# etf_pwr.net
KiCad netlist of a schematic drawn in Altium Designer
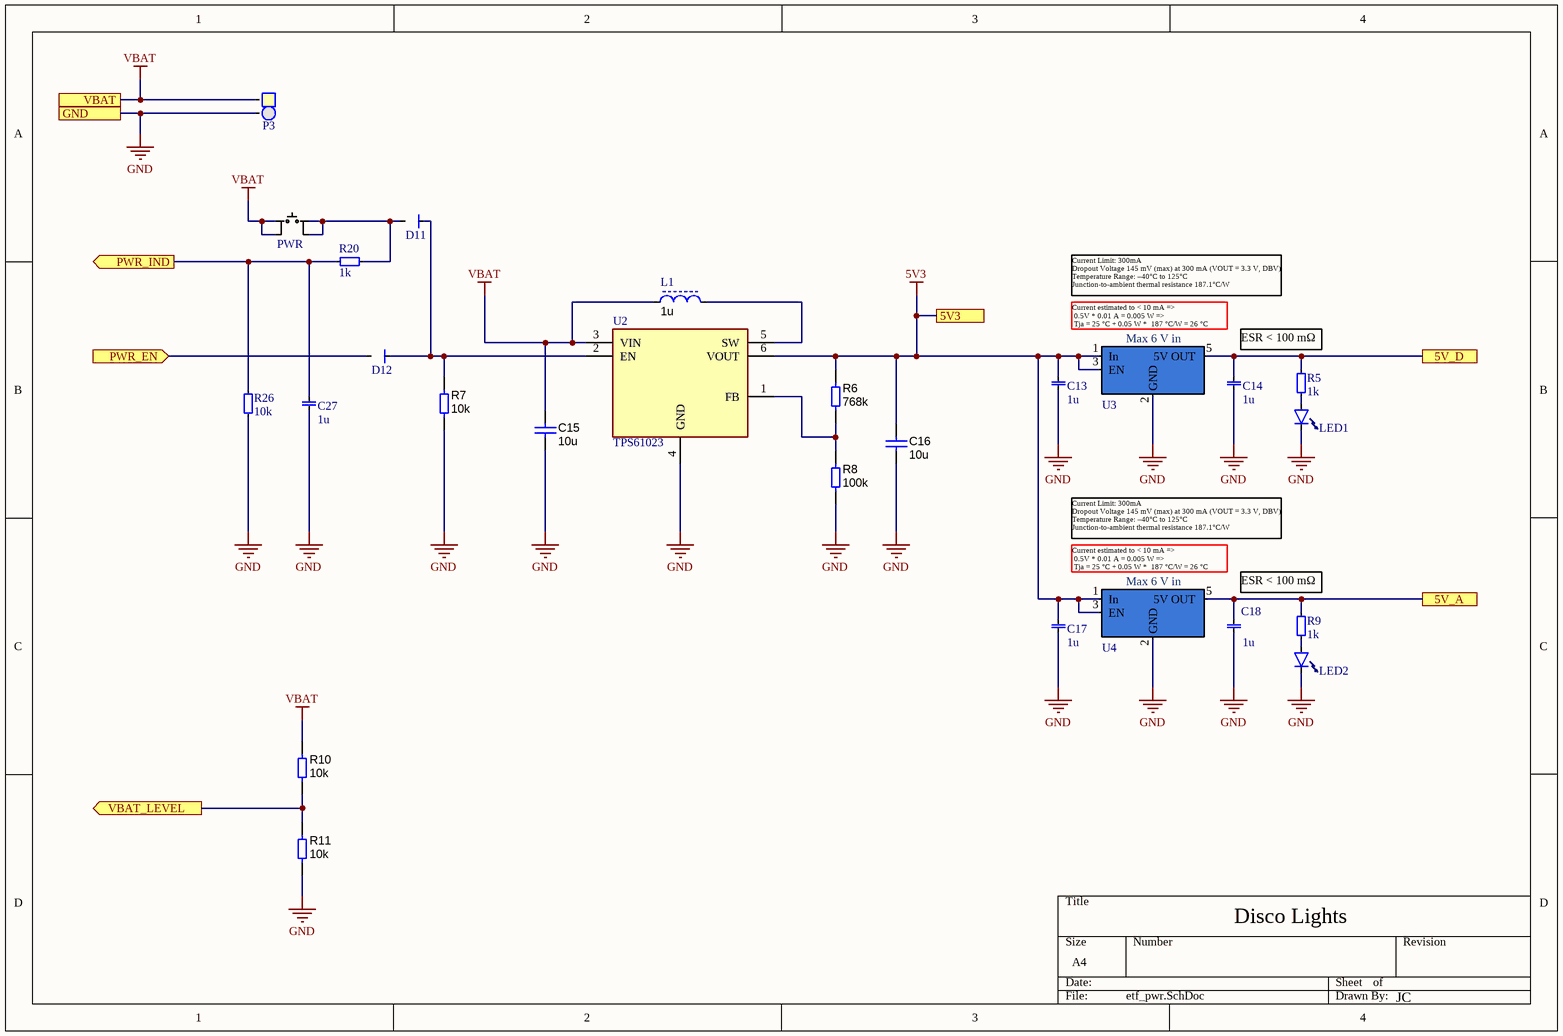
[diagram p0: etf_pwr.SchDoc]

(export (version "E")
  (design (tool "Eeschema 10.0.6"))
  (components
    (comp (ref "C13")
      (value "1u")
      (footprint "0603 cap")
      (fields
        (field (name "JLCPCB PART #") "C77386")
        (field (name "MANUFACTURER PART NUMBER") "GRM188R61H105KAALD")
        (field (name "Comment") "0603, capacitor")
      )
      (libsource (lib "jclib") (part "0603, capacitor"))
    )
    (comp (ref "C14")
      (value "1u")
      (footprint "0603 cap")
      (fields
        (field (name "JLCPCB PART #") "C77386")
        (field (name "MANUFACTURER PART NUMBER") "GRM188R61H105KAALD")
        (field (name "Comment") "0603, capacitor")
      )
      (libsource (lib "jclib") (part "0603, capacitor"))
    )
    (comp (ref "C15")
      (value "10u")
      (footprint "1206_180")
      (fields
        (field (name "JLCPCB PART #") "C342827")
        (field (name "MANUFACTURER PART NUMBER") "C3216X7R1C106KT000N")
        (field (name "Comment") "CAP, 1206")
      )
      (libsource (lib "urad") (part "CAP, 1206"))
    )
    (comp (ref "C16")
      (value "10u")
      (footprint "1206_180")
      (fields
        (field (name "JLCPCB PART #") "C342827")
        (field (name "MANUFACTURER PART NUMBER") "C3216X7R1C106KT000N")
        (field (name "Comment") "CAP, 1206")
      )
      (libsource (lib "urad") (part "CAP, 1206"))
    )
    (comp (ref "C17")
      (value "1u")
      (footprint "0603 cap")
      (fields
        (field (name "JLCPCB PART #") "C77386")
        (field (name "MANUFACTURER PART NUMBER") "GRM188R61H105KAALD")
        (field (name "Comment") "0603, capacitor")
      )
      (libsource (lib "jclib") (part "0603, capacitor"))
    )
    (comp (ref "C18")
      (value "1u")
      (footprint "0603 cap")
      (fields
        (field (name "JLCPCB PART #") "C77386")
        (field (name "MANUFACTURER PART NUMBER") "GRM188R61H105KAALD")
        (field (name "Comment") "0603, capacitor")
      )
      (libsource (lib "jclib") (part "0603, capacitor"))
    )
    (comp (ref "C27")
      (value "1u")
      (footprint "0603 cap")
      (fields
        (field (name "JLCPCB PART #") "C77386")
        (field (name "MANUFACTURER PART NUMBER") "GRM188R61H105KAALD")
        (field (name "Comment") "0603, capacitor")
      )
      (libsource (lib "jclib") (part "0603, capacitor"))
    )
    (comp (ref "D11")
      (value "Diode, SMD")
      (footprint "SOD323")
      (fields (field (name "JLCPCB PART #") "C117941") (field (name "MANUFACTURER PART NUMBER") "BAT760,115"))
      (libsource (lib "jclib") (part "Diode, SMD"))
    )
    (comp (ref "D12")
      (value "Diode, SMD")
      (footprint "SOD323")
      (fields (field (name "JLCPCB PART #") "C117941") (field (name "MANUFACTURER PART NUMBER") "BAT760,115"))
      (libsource (lib "jclib") (part "Diode, SMD"))
    )
    (comp (ref "L1")
      (value "1u")
      (footprint "XEL4030-102MEC")
      (description "Shielded Power Inductor with Ferrite Core")
      (fields
        (field (name "MANUFACTURER PART NUMBER") "XEL4030-102MEC")
        (field (name "Comment") "Inductor, 1616")
      )
      (libsource (lib "urad") (part "Inductor, 1616"))
    )
    (comp (ref "LED1")
      (value "0805, LED")
      (footprint "0805_led")
      (fields
        (field (name "JLCPCB PART #") "C598285")
        (field (name "MANUFACTURER PART NUMBER") "KP-2012SURCK")
      )
      (libsource (lib "jclib") (part "0805, LED"))
    )
    (comp (ref "LED2")
      (value "0805, LED")
      (footprint "0805_led")
      (fields
        (field (name "JLCPCB PART #") "C598285")
        (field (name "MANUFACTURER PART NUMBER") "KP-2012SURCK")
      )
      (libsource (lib "jclib") (part "0805, LED"))
    )
    (comp (ref "P3")
      (value "1x2 Pin Header")
      (footprint "padtwo_L")
      (description "2.54 mm, TH")
      (libsource (lib "jclib") (part "1x2 Pin Header"))
    )
    (comp (ref "PWR")
      (value "Tactile Button")
      (footprint "SW_TS02-66-150-BK-160-LCR-D")
      (description "Tactile Switch Small Low")
      (libsource (lib "urad") (part "TacButton TH"))
    )
    (comp (ref "R5")
      (value "1k")
      (footprint "0603")
      (fields
        (field (name "JLCPCB PART #") "C203217")
        (field (name "MANUFACTURER PART NUMBER") "CR0603-FX-1001ELF")
        (field (name "Comment") "0603, resistor")
      )
      (libsource (lib "jclib") (part "0603, resistor"))
    )
    (comp (ref "R6")
      (value "768k")
      (footprint "0603")
      (fields
        (field (name "JLCPCB PART #") "C245065")
        (field (name "MANUFACTURER PART NUMBER") "CR0603F768KP05Z")
        (field (name "Comment") "RES, 0603")
      )
      (libsource (lib "urad") (part "RES, 0603"))
    )
    (comp (ref "R7")
      (value "10k")
      (footprint "0603")
      (fields
        (field (name "JLCPCB PART #") "C98220")
        (field (name "MANUFACTURER PART NUMBER") "RC0603FR-0710KL")
        (field (name "Comment") "RES, 0603")
      )
      (libsource (lib "urad") (part "RES, 0603"))
    )
    (comp (ref "R8")
      (value "100k")
      (footprint "0603")
      (fields
        (field (name "JLCPCB PART #") "C14675")
        (field (name "MANUFACTURER PART NUMBER") "RC0603FR-07100KL")
        (field (name "Comment") "RES, 0603")
      )
      (libsource (lib "urad") (part "RES, 0603"))
    )
    (comp (ref "R9")
      (value "1k")
      (footprint "0603")
      (fields
        (field (name "JLCPCB PART #") "C203217")
        (field (name "MANUFACTURER PART NUMBER") "CR0603-FX-1001ELF")
        (field (name "Comment") "0603, resistor")
      )
      (libsource (lib "jclib") (part "0603, resistor"))
    )
    (comp (ref "R10")
      (value "10k")
      (footprint "0603")
      (fields
        (field (name "JLCPCB PART #") "C98220")
        (field (name "MANUFACTURER PART NUMBER") "RC0603FR-0710KL")
        (field (name "Comment") "RES, 0603")
      )
      (libsource (lib "urad") (part "RES, 0603"))
    )
    (comp (ref "R11")
      (value "10k")
      (footprint "0603")
      (fields
        (field (name "JLCPCB PART #") "C98220")
        (field (name "MANUFACTURER PART NUMBER") "RC0603FR-0710KL")
        (field (name "Comment") "RES, 0603")
      )
      (libsource (lib "urad") (part "RES, 0603"))
    )
    (comp (ref "R20")
      (value "1k")
      (footprint "0603")
      (fields
        (field (name "JLCPCB PART #") "C203217")
        (field (name "MANUFACTURER PART NUMBER") "CR0603-FX-1001ELF")
        (field (name "Comment") "0603, resistor")
      )
      (libsource (lib "jclib") (part "0603, resistor"))
    )
    (comp (ref "R26")
      (value "10k")
      (footprint "0603")
      (fields
        (field (name "JLCPCB PART #") "C98220")
        (field (name "MANUFACTURER PART NUMBER") "RC0603FR-0710KL")
        (field (name "Comment") "0603, resistor")
      )
      (libsource (lib "jclib") (part "0603, resistor"))
    )
    (comp (ref "U2")
      (value "TPS61023")
      (footprint "SOT50P160X60-6N")
      (description "TPS61023 3.7-A Boost Converter with 0.5-V Ultra-low Input Voltage")
      (fields
        (field (name "JLCPCB PART #") "C919459")
        (field (name "MANUFACTURER PART NUMBER") "TPS61023DRLR")
      )
      (libsource (lib "urad") (part "TPS61023"))
    )
    (comp (ref "U3")
      (value "TPS7A20")
      (footprint "SOT23-5")
      (description "5V and 300-mA, Ultra-Low-Noise, Low-IQ, High PSRR LDO")
      (fields
        (field (name "JLCPCB PART #") "C2873627")
        (field (name "MANUFACTURER PART NUMBER") "TPS7A2045PDBVR")
      )
      (libsource (lib "jclib") (part "TPS7A20"))
    )
    (comp (ref "U4")
      (value "TPS7A20")
      (footprint "SOT23-5")
      (description "5V and 300-mA, Ultra-Low-Noise, Low-IQ, High PSRR LDO")
      (fields
        (field (name "JLCPCB PART #") "C2873627")
        (field (name "MANUFACTURER PART NUMBER") "TPS7A2045PDBVR")
      )
      (libsource (lib "jclib") (part "TPS7A20"))
    )
  )
  (nets
    (net (code "1") (name "/5V_A") (class "Default")
      (node (ref "C18") (pin "1") (pinfunction "1_1") (pintype "passive"))
      (node (ref "R9") (pin "1") (pinfunction "1_1") (pintype "passive"))
      (node (ref "U4") (pin "5") (pinfunction "5V_OUT_5") (pintype "passive"))
    )
    (net (code "2") (name "/5V_D") (class "Default")
      (node (ref "C14") (pin "1") (pinfunction "1_1") (pintype "passive"))
      (node (ref "R5") (pin "1") (pinfunction "1_1") (pintype "passive"))
      (node (ref "U3") (pin "5") (pinfunction "5V_OUT_5") (pintype "passive"))
    )
    (net (code "3") (name "/PWR_EN") (class "Default")
      (node (ref "D12") (pin "2") (pinfunction "2_2") (pintype "passive"))
    )
    (net (code "4") (name "/PWR_IND") (class "Default")
      (node (ref "C27") (pin "1") (pinfunction "1_1") (pintype "passive"))
      (node (ref "R20") (pin "0") (pinfunction "0_0") (pintype "passive"))
      (node (ref "R26") (pin "1") (pinfunction "1_1") (pintype "passive"))
    )
    (net (code "5") (name "/VBAT_LEVEL") (class "Default")
      (node (ref "R10") (pin "1") (pinfunction "1_1") (pintype "passive"))
      (node (ref "R11") (pin "2") (pinfunction "2_2") (pintype "passive"))
    )
    (net (code "6") (name "5V3") (class "Default")
      (node (ref "C13") (pin "1") (pinfunction "1_1") (pintype "passive"))
      (node (ref "C16") (pin "1") (pinfunction "1_1") (pintype "passive"))
      (node (ref "C17") (pin "1") (pinfunction "1_1") (pintype "passive"))
      (node (ref "R6") (pin "2") (pinfunction "2_2") (pintype "passive"))
      (node (ref "U2") (pin "6") (pinfunction "VOUT_6") (pintype "passive"))
      (node (ref "U3") (pin "1") (pinfunction "In_1") (pintype "passive"))
      (node (ref "U3") (pin "3") (pinfunction "EN_3") (pintype "passive"))
      (node (ref "U4") (pin "1") (pinfunction "In_1") (pintype "passive"))
      (node (ref "U4") (pin "3") (pinfunction "EN_3") (pintype "passive"))
    )
    (net (code "7") (name "GND") (class "Default")
      (node (ref "C13") (pin "0") (pinfunction "0_0") (pintype "passive"))
      (node (ref "C14") (pin "0") (pinfunction "0_0") (pintype "passive"))
      (node (ref "C15") (pin "2") (pinfunction "2_2") (pintype "passive"))
      (node (ref "C16") (pin "2") (pinfunction "2_2") (pintype "passive"))
      (node (ref "C17") (pin "0") (pinfunction "0_0") (pintype "passive"))
      (node (ref "C18") (pin "0") (pinfunction "0_0") (pintype "passive"))
      (node (ref "C27") (pin "0") (pinfunction "0_0") (pintype "passive"))
      (node (ref "LED1") (pin "0") (pinfunction "Cathode_0") (pintype "passive"))
      (node (ref "LED2") (pin "0") (pinfunction "Cathode_0") (pintype "passive"))
      (node (ref "P3") (pin "2") (pinfunction "2_2") (pintype "passive"))
      (node (ref "R11") (pin "1") (pinfunction "1_1") (pintype "passive"))
      (node (ref "R26") (pin "0") (pinfunction "0_0") (pintype "passive"))
      (node (ref "R7") (pin "1") (pinfunction "1_1") (pintype "passive"))
      (node (ref "R8") (pin "1") (pinfunction "1_1") (pintype "passive"))
      (node (ref "U2") (pin "4") (pinfunction "GND_4") (pintype "power_in"))
      (node (ref "U3") (pin "2") (pinfunction "GND_2") (pintype "passive"))
      (node (ref "U4") (pin "2") (pinfunction "GND_2") (pintype "passive"))
    )
    (net (code "8") (name "Net-(D11-Pad2)") (class "Default")
      (node (ref "D11") (pin "2") (pinfunction "2_2") (pintype "passive"))
      (node (ref "PWR") (pin "1") (pinfunction "1_1") (pintype "passive"))
      (node (ref "PWR") (pin "2") (pinfunction "2_2") (pintype "passive"))
      (node (ref "R20") (pin "1") (pinfunction "1_1") (pintype "passive"))
    )
    (net (code "9") (name "Net-(LED1-Pad1)") (class "Default")
      (node (ref "LED1") (pin "1") (pinfunction "1_1") (pintype "passive"))
      (node (ref "R5") (pin "0") (pinfunction "0_0") (pintype "passive"))
    )
    (net (code "10") (name "Net-(LED2-Pad1)") (class "Default")
      (node (ref "LED2") (pin "1") (pinfunction "1_1") (pintype "passive"))
      (node (ref "R9") (pin "0") (pinfunction "0_0") (pintype "passive"))
    )
    (net (code "11") (name "Net-(U2-EN)") (class "Default")
      (node (ref "D11") (pin "1") (pinfunction "1_1") (pintype "passive"))
      (node (ref "D12") (pin "1") (pinfunction "1_1") (pintype "passive"))
      (node (ref "R7") (pin "2") (pinfunction "2_2") (pintype "passive"))
      (node (ref "U2") (pin "2") (pinfunction "EN_2") (pintype "passive"))
    )
    (net (code "12") (name "Net-(U2-FB)") (class "Default")
      (node (ref "R6") (pin "1") (pinfunction "1_1") (pintype "passive"))
      (node (ref "R8") (pin "2") (pinfunction "2_2") (pintype "passive"))
      (node (ref "U2") (pin "1") (pinfunction "FB_1") (pintype "passive"))
    )
    (net (code "13") (name "Net-(U2-SW)") (class "Default")
      (node (ref "L1") (pin "1") (pinfunction "1_1") (pintype "passive"))
      (node (ref "U2") (pin "5") (pinfunction "SW_5") (pintype "passive"))
    )
    (net (code "14") (name "VBAT") (class "Default")
      (node (ref "C15") (pin "1") (pinfunction "1_1") (pintype "passive"))
      (node (ref "L1") (pin "2") (pinfunction "2_2") (pintype "passive"))
      (node (ref "P3") (pin "1") (pinfunction "1_1") (pintype "passive"))
      (node (ref "PWR") (pin "3") (pinfunction "3_3") (pintype "passive"))
      (node (ref "PWR") (pin "4") (pinfunction "4_4") (pintype "passive"))
      (node (ref "R10") (pin "2") (pinfunction "2_2") (pintype "passive"))
      (node (ref "U2") (pin "3") (pinfunction "VIN_3") (pintype "passive"))
    )
  )
)
